# UV_Sheet1.net
KiCad netlist of a schematic drawn in Altium Designer
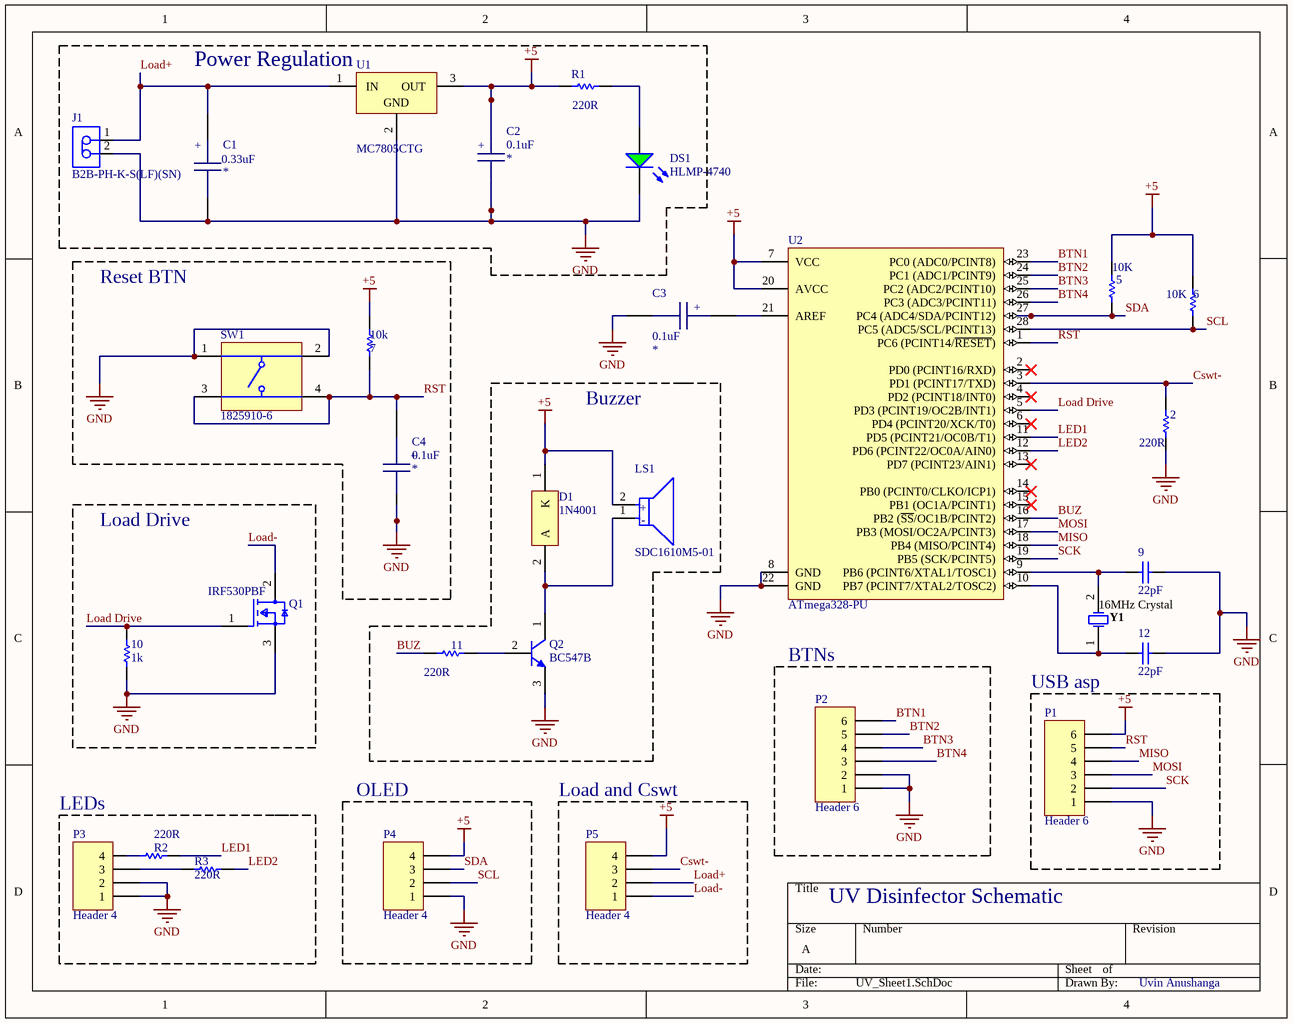
[diagram p0: UV_Sheet1.SchDoc]

(export (version "E")
  (design (tool "Eeschema 10.0.6"))
  (components
    (comp (ref "2")
      (value "220R")
      (footprint "RESA60-630X240")
      (description "Axial Resistor, 100 KOhm, +/- 1%, 0.25 W, -55 to 155 degC, 2-Pin THD, RoHS, Bulk")
      (fields (field (name "TOLERANCE") "1%"))
      (libsource (lib "Altium Content Vault") (part "RES-2"))
    )
    (comp (ref "5")
      (value "10K")
      (footprint "RESA60-630X240")
      (description "Axial Resistor, 100 KOhm, +/- 1%, 0.25 W, -55 to 155 degC, 2-Pin THD, RoHS, Bulk")
      (fields (field (name "TOLERANCE") "1%"))
      (libsource (lib "Altium Content Vault") (part "RES-2"))
    )
    (comp (ref "6")
      (value "10K")
      (footprint "RESA60-630X240")
      (description "Axial Resistor, 100 KOhm, +/- 1%, 0.25 W, -55 to 155 degC, 2-Pin THD, RoHS, Bulk")
      (fields (field (name "TOLERANCE") "1%"))
      (libsource (lib "Altium Content Vault") (part "RES-2"))
    )
    (comp (ref "7")
      (value "10k")
      (footprint "RESA60-630X240")
      (description "Axial Resistor, 100 KOhm, +/- 1%, 0.25 W, -55 to 155 degC, 2-Pin THD, RoHS, Bulk")
      (fields (field (name "TOLERANCE") "1%"))
      (libsource (lib "Altium Content Vault") (part "RES-2"))
    )
    (comp (ref "9")
      (value "22pF")
      (footprint "KEMT-C315-THT-2")
      (description "Capacitor, Ceramic, 22 pF, +/-10 %, 100 V, -55 to 125 degC, 2-Pin THD, RoHS, Bulk")
      (libsource (lib "Altium Content Vault") (part "CAP-NP-2"))
    )
    (comp (ref "10")
      (value "1k")
      (footprint "RESA60-630X240")
      (description "Axial Resistor, 100 KOhm, +/- 1%, 0.25 W, -55 to 155 degC, 2-Pin THD, RoHS, Bulk")
      (fields (field (name "TOLERANCE") "1%"))
      (libsource (lib "Altium Content Vault") (part "RES-2"))
    )
    (comp (ref "11")
      (value "220R")
      (footprint "RESA60-630X240")
      (description "Axial Resistor, 100 KOhm, +/- 1%, 0.25 W, -55 to 155 degC, 2-Pin THD, RoHS, Bulk")
      (fields (field (name "TOLERANCE") "1%"))
      (libsource (lib "Altium Content Vault") (part "RES-2"))
    )
    (comp (ref "12")
      (value "22pF")
      (footprint "KEMT-C315-THT-2")
      (description "Capacitor, Ceramic, 22 pF, +/-10 %, 100 V, -55 to 125 degC, 2-Pin THD, RoHS, Bulk")
      (libsource (lib "Altium Content Vault") (part "CAP-NP-2"))
    )
    (comp (ref "C1")
      (value "0.33uF")
      (footprint "Cap NP")
      (fields (field (name "ALTIUM_VALUE") "*"))
      (libsource (lib "Funcgen") (part "Cap_NP"))
    )
    (comp (ref "C2")
      (value "0.1uF")
      (footprint "Cap NP")
      (fields (field (name "ALTIUM_VALUE") "*"))
      (libsource (lib "Funcgen") (part "Cap_NP"))
    )
    (comp (ref "C3")
      (value "0.1uF")
      (footprint "Cap NP")
      (fields (field (name "ALTIUM_VALUE") "*"))
      (libsource (lib "Funcgen") (part "Cap_NP"))
    )
    (comp (ref "C4")
      (value "0.1uF")
      (footprint "Cap NP")
      (fields (field (name "ALTIUM_VALUE") "*"))
      (libsource (lib "Funcgen") (part "Cap_NP"))
    )
    (comp (ref "D1")
      (value "1N4001")
      (footprint "ONSC-AXIAL_LEAD-2-59-10_P")
      (description "Standard Recovery Rectifier, 2-Pin Axial_Lead, Pb-Free, Bulk Bag")
      (fields (field (name "MANUFACTURER") "On Semiconductor"))
      (libsource (lib "Altium Content Vault") (part "ONSC-D-K1A2-2_A"))
    )
    (comp (ref "DS1")
      (value "HLMP-4740")
      (footprint "AVAG-HLMP-4740")
      (description "T-1 3/4 (5 mm) Low Current LED Lamp, Green, 1.9 V, -20 to 100 degC, 2-Pin THD, RoHS, Bulk")
      (fields (field (name "MANUFACTURER") "AvagoTechnologies"))
      (libsource (lib "Altium Content Vault") (part "LED-GREEN-AK-2"))
    )
    (comp (ref "J1")
      (value "B2B-PH-K-S(LF)(SN)")
      (footprint "JST-B2B-PH-K-S_V")
      (fields (field (name "MANUFACTURER") "JST"))
      (libsource (lib "Altium Content Vault") (part "CN-2P-F-QF2"))
    )
    (comp (ref "LS1")
      (value "SDC1610M5-01")
      (footprint "FP-SDC1610M5-01-MFG")
      (description "AUDIO MAGNETIC INDICATOR 4-8V TH")
      (libsource (lib "Altium Content Vault") (part "f7ec632b6fea80cbef86dc3340f200c"))
    )
    (comp (ref "P1")
      (value "Header 6")
      (footprint "HDR1X6")
      (description "Header, 6-Pin")
      (fields (field (name "PUBLISHER") "Altium Limited"))
      (libsource (lib "Miscellaneous Connectors") (part "Header 6"))
    )
    (comp (ref "P2")
      (value "Header 6")
      (footprint "HDR1X6")
      (description "Header, 6-Pin")
      (fields (field (name "PUBLISHER") "Altium Limited"))
      (libsource (lib "Miscellaneous Connectors") (part "Header 6"))
    )
    (comp (ref "P3")
      (value "Header 4")
      (footprint "HDR1X4")
      (description "Header, 4-Pin")
      (fields (field (name "PUBLISHER") "Altium Limited"))
      (libsource (lib "Miscellaneous Connectors") (part "Header 4"))
    )
    (comp (ref "P4")
      (value "Header 4")
      (footprint "HDR1X4")
      (description "Header, 4-Pin")
      (fields (field (name "PUBLISHER") "Altium Limited"))
      (libsource (lib "Miscellaneous Connectors") (part "Header 4"))
    )
    (comp (ref "P5")
      (value "Header 4")
      (footprint "HDR1X4")
      (description "Header, 4-Pin")
      (fields (field (name "PUBLISHER") "Altium Limited"))
      (libsource (lib "Miscellaneous Connectors") (part "Header 4"))
    )
    (comp (ref "Q1")
      (value "IRF530PBF")
      (footprint "FP-X15-0364-MFG")
      (description "MOSFET N-CH 100V 14A TO-220AB")
      (fields
        (field (name "MANUFACTURER") "Vishay")
        (field (name "OCTOPART") "https://octopart.com/irf530pbf-vishay-46547999")
      )
      (libsource (lib "Altium Content Vault") (part "277670f45256a45703965f138927d09"))
    )
    (comp (ref "Q2")
      (value "BC547B")
      (footprint "ONSC-TO-92-3-29-11")
      (description "Amplifier Transistor, NPN Silicon, 3-Pin TO-92, Bulk Box")
      (fields (field (name "MANUFACTURER") "On Semiconductor"))
      (libsource (lib "Altium Content Vault") (part "ONSC-NPN-C1B2E3-3"))
    )
    (comp (ref "R1")
      (value "220R")
      (footprint "RESA60-630X240")
      (description "Axial Resistor, 100 KOhm, +/- 1%, 0.25 W, -55 to 155 degC, 2-Pin THD, RoHS, Bulk")
      (fields (field (name "TOLERANCE") "1%"))
      (libsource (lib "Altium Content Vault") (part "RES-2"))
    )
    (comp (ref "R2")
      (value "220R")
      (footprint "RESA60-630X240")
      (description "Axial Resistor, 100 KOhm, +/- 1%, 0.25 W, -55 to 155 degC, 2-Pin THD, RoHS, Bulk")
      (fields (field (name "TOLERANCE") "1%"))
      (libsource (lib "Altium Content Vault") (part "RES-2"))
    )
    (comp (ref "R3")
      (value "220R")
      (footprint "RESA60-630X240")
      (description "Axial Resistor, 100 KOhm, +/- 1%, 0.25 W, -55 to 155 degC, 2-Pin THD, RoHS, Bulk")
      (fields (field (name "TOLERANCE") "1%"))
      (libsource (lib "Altium Content Vault") (part "RES-2"))
    )
    (comp (ref "SW1")
      (value "1825910-6")
      (footprint "TECO-1825910-6_V")
      (description "Tact Switch, SPST-NO, 0.05 A, -35 to 85 degC, 4-Pin THD, RoHS, Bulk")
      (fields (field (name "MANUFACTURER") "TE Connectivity"))
      (libsource (lib "Altium Content Vault") (part "SW-SPST-4_A"))
    )
    (comp (ref "U1")
      (value "MC7805CTG")
      (footprint "ONSC-TO-220-3-221AB-01")
      (description "Positive Voltage Regulator, 1 A, 5 V, 0 to 125 degC, 3-Pin TO-220, RoHS, Tube")
      (fields (field (name "MANUFACTURER") "ON Semiconductor"))
      (libsource (lib "Altium Content Vault") (part "ONSC-MC7805CTG-TO-220-3"))
    )
    (comp (ref "U2")
      (value "ATmega328-PU")
      (footprint "28P3")
      (libsource (lib "Altium Content Vault") (part "MC-8B-ATM48-IL28"))
    )
    (comp (ref "Y1")
      (value "16MHz Crystal")
      (footprint "FOX-FOXSLF080-20")
      (description "Resistance Weld Thru-Hole Crystal, 8 MHz, +/- 50 ppm, 10 pF, -20 to 70 degC, 2-Pin THD, RoHS, Bulk")
      (fields (field (name "MANUFACTURER") "FOX Electronics") (field (name "TOLERANCE") "50ppm"))
      (libsource (lib "University of Moratuwa") (part "XTAL-1-2-2"))
    )
  )
  (nets
    (net (code "1") (name "+5") (class "Default")
      (node (ref "5") (pin "2") (pinfunction "2_2") (pintype "passive"))
      (node (ref "6") (pin "2") (pinfunction "2_2") (pintype "passive"))
      (node (ref "7") (pin "2") (pinfunction "2_2") (pintype "passive"))
      (node (ref "C2") (pin "2") (pinfunction "2_2") (pintype "passive"))
      (node (ref "D1") (pin "1") (pinfunction "K_1") (pintype "passive"))
      (node (ref "LS1") (pin "2") (pinfunction "A_2") (pintype "passive"))
      (node (ref "P1") (pin "6") (pinfunction "6_6") (pintype "passive"))
      (node (ref "P4") (pin "4") (pinfunction "4_4") (pintype "passive"))
      (node (ref "P5") (pin "4") (pinfunction "4_4") (pintype "passive"))
      (node (ref "R1") (pin "1") (pinfunction "1_1") (pintype "passive"))
      (node (ref "U1") (pin "3") (pinfunction "OUT_3") (pintype "power_in"))
      (node (ref "U2") (pin "20") (pinfunction "AVCC_20") (pintype "power_in"))
      (node (ref "U2") (pin "7") (pinfunction "VCC_7") (pintype "power_in"))
    )
    (net (code "2") (name "/BTN1") (class "Default")
      (node (ref "P2") (pin "6") (pinfunction "6_6") (pintype "passive"))
      (node (ref "U2") (pin "23") (pinfunction "PC0_(ADC0/PCINT8)_23") (pintype "bidirectional"))
    )
    (net (code "3") (name "/BTN2") (class "Default")
      (node (ref "P2") (pin "5") (pinfunction "5_5") (pintype "passive"))
      (node (ref "U2") (pin "24") (pinfunction "PC1_(ADC1/PCINT9)_24") (pintype "bidirectional"))
    )
    (net (code "4") (name "/BTN3") (class "Default")
      (node (ref "P2") (pin "4") (pinfunction "4_4") (pintype "passive"))
      (node (ref "U2") (pin "25") (pinfunction "PC2_(ADC2/PCINT10)_25") (pintype "bidirectional"))
    )
    (net (code "5") (name "/BTN4") (class "Default")
      (node (ref "P2") (pin "3") (pinfunction "3_3") (pintype "passive"))
      (node (ref "U2") (pin "26") (pinfunction "PC3_(ADC3/PCINT11)_26") (pintype "bidirectional"))
    )
    (net (code "6") (name "/BUZ") (class "Default")
      (node (ref "11") (pin "1") (pinfunction "1_1") (pintype "passive"))
      (node (ref "U2") (pin "16") (pinfunction "PB2_(~{SS}/OC1B/PCINT2)_16") (pintype "bidirectional"))
    )
    (net (code "7") (name "/Cswt-") (class "Default")
      (node (ref "2") (pin "2") (pinfunction "2_2") (pintype "passive"))
      (node (ref "P5") (pin "3") (pinfunction "3_3") (pintype "passive"))
      (node (ref "U2") (pin "3") (pinfunction "PD1_(PCINT17/TXD)_3") (pintype "bidirectional"))
    )
    (net (code "8") (name "/LED1") (class "Default")
      (node (ref "R2") (pin "2") (pinfunction "2_2") (pintype "passive"))
      (node (ref "U2") (pin "11") (pinfunction "PD5_(PCINT21/OC0B/T1)_11") (pintype "bidirectional"))
    )
    (net (code "9") (name "/LED2") (class "Default")
      (node (ref "R3") (pin "2") (pinfunction "2_2") (pintype "passive"))
      (node (ref "U2") (pin "12") (pinfunction "PD6_(PCINT22/OC0A/AIN0)_12") (pintype "bidirectional"))
    )
    (net (code "10") (name "/Load Drive") (class "Default")
      (node (ref "10") (pin "2") (pinfunction "2_2") (pintype "passive"))
      (node (ref "Q1") (pin "1") (pinfunction "G_1") (pintype "passive"))
      (node (ref "U2") (pin "5") (pinfunction "PD3_(PCINT19/OC2B/INT1)_5") (pintype "bidirectional"))
    )
    (net (code "11") (name "/Load+") (class "Default")
      (node (ref "C1") (pin "1") (pinfunction "1_1") (pintype "passive"))
      (node (ref "J1") (pin "1") (pinfunction "1_1") (pintype "passive"))
      (node (ref "P5") (pin "2") (pinfunction "2_2") (pintype "passive"))
      (node (ref "U1") (pin "1") (pinfunction "IN_1") (pintype "power_in"))
    )
    (net (code "12") (name "/Load-") (class "Default")
      (node (ref "P5") (pin "1") (pinfunction "1_1") (pintype "passive"))
      (node (ref "Q1") (pin "2") (pinfunction "D_2") (pintype "passive"))
    )
    (net (code "13") (name "/MISO") (class "Default")
      (node (ref "P1") (pin "4") (pinfunction "4_4") (pintype "passive"))
      (node (ref "U2") (pin "18") (pinfunction "PB4_(MISO/PCINT4)_18") (pintype "bidirectional"))
    )
    (net (code "14") (name "/MOSI") (class "Default")
      (node (ref "P1") (pin "3") (pinfunction "3_3") (pintype "passive"))
      (node (ref "U2") (pin "17") (pinfunction "PB3_(MOSI/OC2A/PCINT3)_17") (pintype "bidirectional"))
    )
    (net (code "15") (name "/RST") (class "Default")
      (node (ref "7") (pin "1") (pinfunction "1_1") (pintype "passive"))
      (node (ref "C4") (pin "2") (pinfunction "2_2") (pintype "passive"))
      (node (ref "P1") (pin "5") (pinfunction "5_5") (pintype "passive"))
      (node (ref "SW1") (pin "3") (pinfunction "3_3") (pintype "passive"))
      (node (ref "SW1") (pin "4") (pinfunction "4_4") (pintype "passive"))
      (node (ref "U2") (pin "1") (pinfunction "PC6_(PCINT14/~{RESET})_1") (pintype "bidirectional"))
    )
    (net (code "16") (name "/SCK") (class "Default")
      (node (ref "P1") (pin "2") (pinfunction "2_2") (pintype "passive"))
      (node (ref "U2") (pin "19") (pinfunction "PB5_(SCK/PCINT5)_19") (pintype "bidirectional"))
    )
    (net (code "17") (name "/SCL") (class "Default")
      (node (ref "6") (pin "1") (pinfunction "1_1") (pintype "passive"))
      (node (ref "P4") (pin "2") (pinfunction "2_2") (pintype "passive"))
      (node (ref "U2") (pin "28") (pinfunction "PC5_(ADC5/SCL/PCINT13)_28") (pintype "bidirectional"))
    )
    (net (code "18") (name "/SDA") (class "Default")
      (node (ref "5") (pin "1") (pinfunction "1_1") (pintype "passive"))
      (node (ref "P4") (pin "3") (pinfunction "3_3") (pintype "passive"))
      (node (ref "U2") (pin "27") (pinfunction "PC4_(ADC4/SDA/PCINT12)_27") (pintype "bidirectional"))
    )
    (net (code "19") (name "GND") (class "Default")
      (node (ref "10") (pin "1") (pinfunction "1_1") (pintype "passive"))
      (node (ref "12") (pin "2") (pinfunction "2_2") (pintype "passive"))
      (node (ref "2") (pin "1") (pinfunction "1_1") (pintype "passive"))
      (node (ref "9") (pin "2") (pinfunction "2_2") (pintype "passive"))
      (node (ref "C1") (pin "2") (pinfunction "2_2") (pintype "passive"))
      (node (ref "C2") (pin "1") (pinfunction "1_1") (pintype "passive"))
      (node (ref "C3") (pin "2") (pinfunction "2_2") (pintype "passive"))
      (node (ref "C4") (pin "1") (pinfunction "1_1") (pintype "passive"))
      (node (ref "DS1") (pin "2") (pinfunction "K_2") (pintype "passive"))
      (node (ref "J1") (pin "2") (pinfunction "2_2") (pintype "passive"))
      (node (ref "P1") (pin "1") (pinfunction "1_1") (pintype "passive"))
      (node (ref "P2") (pin "1") (pinfunction "1_1") (pintype "passive"))
      (node (ref "P2") (pin "2") (pinfunction "2_2") (pintype "passive"))
      (node (ref "P3") (pin "1") (pinfunction "1_1") (pintype "passive"))
      (node (ref "P3") (pin "2") (pinfunction "2_2") (pintype "passive"))
      (node (ref "P4") (pin "1") (pinfunction "1_1") (pintype "passive"))
      (node (ref "Q1") (pin "3") (pinfunction "S_3") (pintype "passive"))
      (node (ref "Q2") (pin "3") (pinfunction "E_3") (pintype "passive"))
      (node (ref "SW1") (pin "1") (pinfunction "1_1") (pintype "passive"))
      (node (ref "SW1") (pin "2") (pinfunction "2_2") (pintype "passive"))
      (node (ref "U1") (pin "2") (pinfunction "GND_2") (pintype "power_in"))
      (node (ref "U2") (pin "22") (pinfunction "GND_22") (pintype "power_in"))
      (node (ref "U2") (pin "8") (pinfunction "GND_8") (pintype "power_in"))
    )
    (net (code "20") (name "Net-(D1-A)") (class "Default")
      (node (ref "D1") (pin "2") (pinfunction "A_2") (pintype "passive"))
      (node (ref "LS1") (pin "1") (pinfunction "C_1") (pintype "passive"))
      (node (ref "Q2") (pin "1") (pinfunction "C_1") (pintype "passive"))
    )
    (net (code "21") (name "Net-(DS1-A)") (class "Default")
      (node (ref "DS1") (pin "1") (pinfunction "A_1") (pintype "passive"))
      (node (ref "R1") (pin "2") (pinfunction "2_2") (pintype "passive"))
    )
    (net (code "22") (name "Net-(P3-Pad3)") (class "Default")
      (node (ref "P3") (pin "3") (pinfunction "3_3") (pintype "passive"))
      (node (ref "R3") (pin "1") (pinfunction "1_1") (pintype "passive"))
    )
    (net (code "23") (name "Net-(P3-Pad4)") (class "Default")
      (node (ref "P3") (pin "4") (pinfunction "4_4") (pintype "passive"))
      (node (ref "R2") (pin "1") (pinfunction "1_1") (pintype "passive"))
    )
    (net (code "24") (name "Net-(Q2-B)") (class "Default")
      (node (ref "11") (pin "2") (pinfunction "2_2") (pintype "passive"))
      (node (ref "Q2") (pin "2") (pinfunction "B_2") (pintype "passive"))
    )
    (net (code "25") (name "Net-(U2-AREF)") (class "Default")
      (node (ref "C3") (pin "1") (pinfunction "1_1") (pintype "passive"))
      (node (ref "U2") (pin "21") (pinfunction "AREF_21") (pintype "power_in"))
    )
    (net (code "26") (name "Net-(U2-PB6_(PCINT6{slash}XTAL1{slash}TOSC1))") (class "Default")
      (node (ref "9") (pin "1") (pinfunction "1_1") (pintype "passive"))
      (node (ref "U2") (pin "9") (pinfunction "PB6_(PCINT6/XTAL1/TOSC1)_9") (pintype "bidirectional"))
      (node (ref "Y1") (pin "2") (pinfunction "2_2") (pintype "passive"))
    )
    (net (code "27") (name "Net-(U2-PB7_(PCINT7{slash}XTAL2{slash}TOSC2))") (class "Default")
      (node (ref "12") (pin "1") (pinfunction "1_1") (pintype "passive"))
      (node (ref "U2") (pin "10") (pinfunction "PB7_(PCINT7/XTAL2/TOSC2)_10") (pintype "bidirectional"))
      (node (ref "Y1") (pin "1") (pinfunction "1_1") (pintype "passive"))
    )
    (net (code "28") (name "unconnected-(U2-PB0_(PCINT0{slash}CLKO{slash}ICP1)-Pad14)") (class "Default")
      (node (ref "U2") (pin "14") (pinfunction "PB0_(PCINT0/CLKO/ICP1)_14") (pintype "bidirectional+no_connect"))
    )
    (net (code "29") (name "unconnected-(U2-PB1_(OC1A{slash}PCINT1)-Pad15)") (class "Default")
      (node (ref "U2") (pin "15") (pinfunction "PB1_(OC1A/PCINT1)_15") (pintype "bidirectional+no_connect"))
    )
    (net (code "30") (name "unconnected-(U2-PD0_(PCINT16{slash}RXD)-Pad2)") (class "Default")
      (node (ref "U2") (pin "2") (pinfunction "PD0_(PCINT16/RXD)_2") (pintype "bidirectional+no_connect"))
    )
    (net (code "31") (name "unconnected-(U2-PD2_(PCINT18{slash}INT0)-Pad4)") (class "Default")
      (node (ref "U2") (pin "4") (pinfunction "PD2_(PCINT18/INT0)_4") (pintype "bidirectional+no_connect"))
    )
    (net (code "32") (name "unconnected-(U2-PD4_(PCINT20{slash}XCK{slash}T0)-Pad6)") (class "Default")
      (node (ref "U2") (pin "6") (pinfunction "PD4_(PCINT20/XCK/T0)_6") (pintype "bidirectional+no_connect"))
    )
    (net (code "33") (name "unconnected-(U2-PD7_(PCINT23{slash}AIN1)-Pad13)") (class "Default")
      (node (ref "U2") (pin "13") (pinfunction "PD7_(PCINT23/AIN1)_13") (pintype "bidirectional+no_connect"))
    )
  )
)
